# diagnostic-main.net
KiCad netlist of a schematic drawn in EAGLE
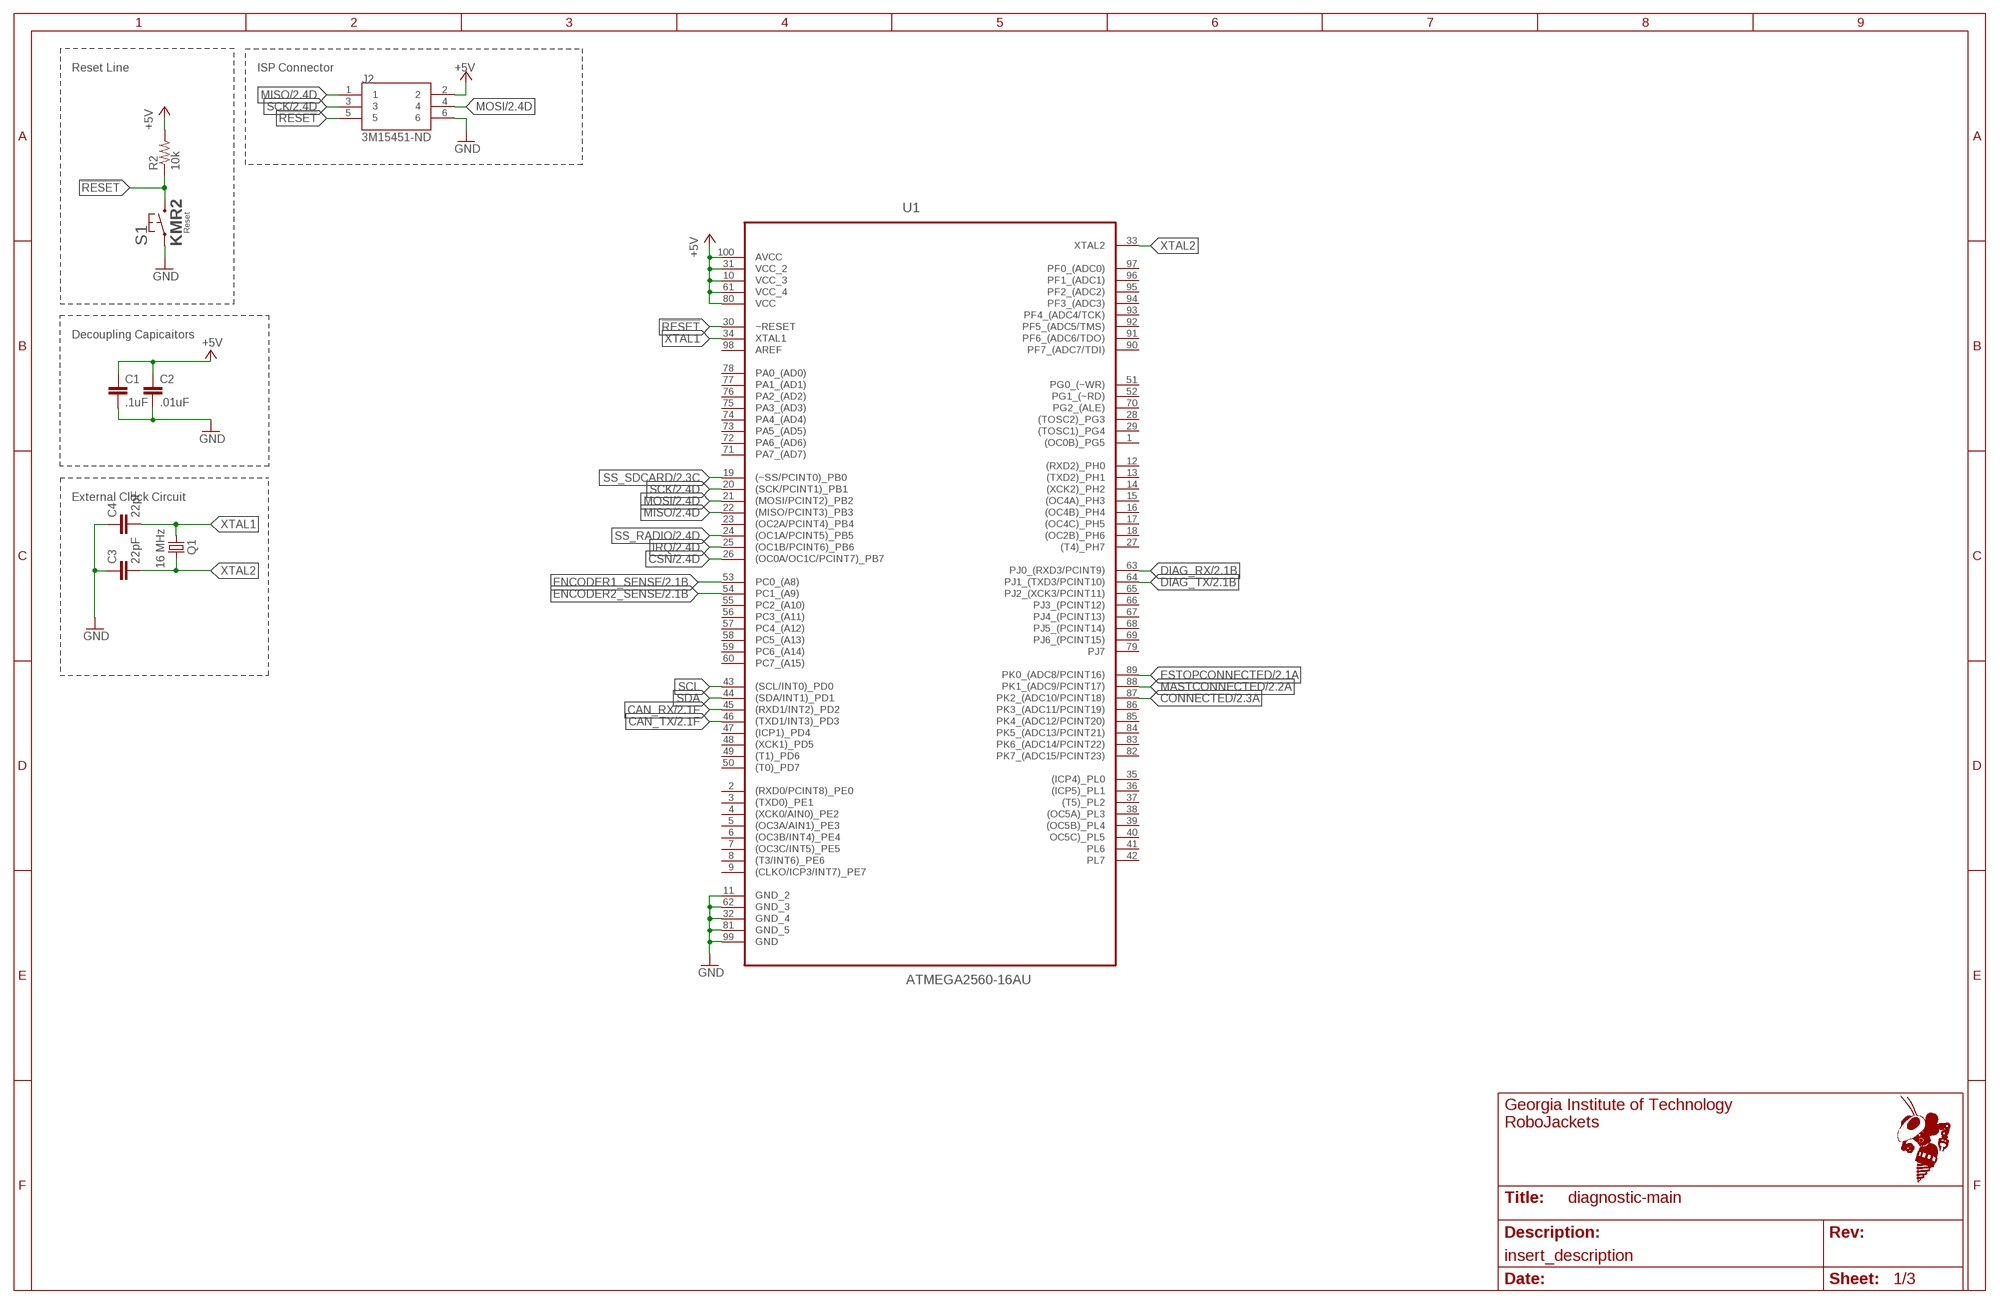
[diagram p0: schematic, sheet 1]
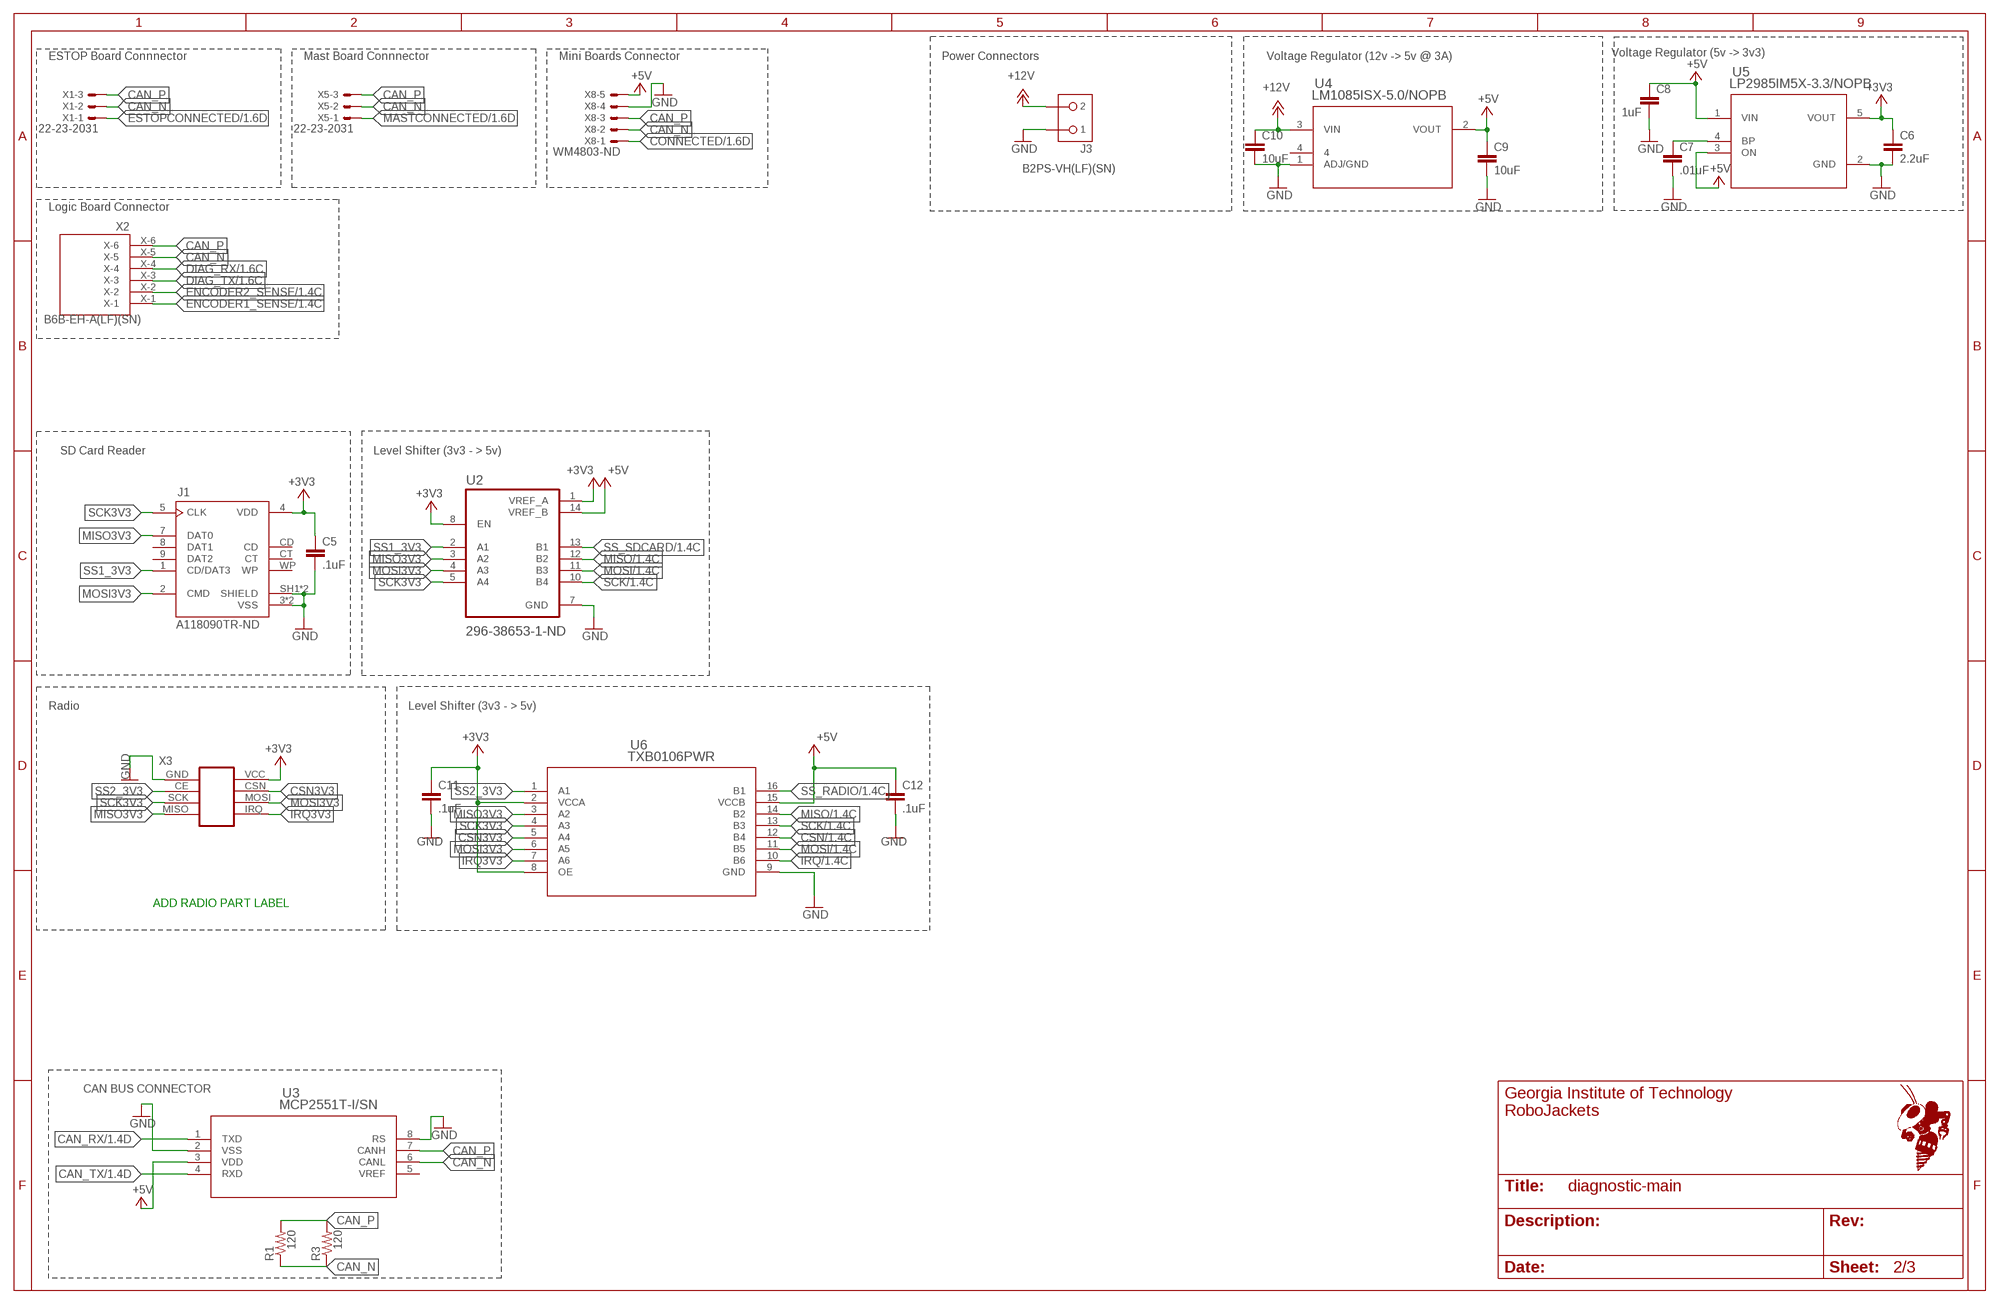
[diagram p1: schematic, sheet 2]

(export (version "E")
  (design (tool "Eeschema 10.0.6"))
  (components
    (comp (ref "C5")
      (value ".1uF")
      (footprint "eagle-import:C0603")
      (libsource (lib "eagle-import") (part "C-EUC0603"))
    )
    (comp (ref "C6")
      (value "2.2uF")
      (footprint "eagle-import:C0603")
      (libsource (lib "eagle-import") (part "C-EUC0603"))
    )
    (comp (ref "C7")
      (value ".01uF")
      (footprint "eagle-import:C0603")
      (libsource (lib "eagle-import") (part "C-EUC0603"))
    )
    (comp (ref "C8")
      (value "1uF")
      (footprint "eagle-import:C0603")
      (libsource (lib "eagle-import") (part "C-EUC0603"))
    )
    (comp (ref "C9")
      (value "10uF")
      (footprint "eagle-import:C0805")
      (libsource (lib "eagle-import") (part "C-EUC0805"))
    )
    (comp (ref "C10")
      (value "10uF")
      (footprint "eagle-import:C0805")
      (libsource (lib "eagle-import") (part "C-EUC0805"))
    )
    (comp (ref "C11")
      (value ".1uF")
      (footprint "eagle-import:C0603")
      (libsource (lib "eagle-import") (part "C-EUC0603"))
    )
    (comp (ref "C12")
      (value ".1uF")
      (footprint "eagle-import:C0603")
      (libsource (lib "eagle-import") (part "C-EUC0603"))
    )
    (comp (ref "J1")
      (value "A118090TR-ND")
      (footprint "eagle-import:TE_1939870-1")
      (fields
        (field (name "COMMENT") "1939870-1")
        (field (name "DIGI-KEY_PART_NUMBER") "A118090CT-ND")
        (field (name "MF") "TE Connectivity")
      )
      (libsource (lib "eagle-import") (part "1939870-1"))
    )
    (comp (ref "J3")
      (value "B2PS-VH(LF)(SN)")
      (footprint "eagle-import:B2PS-CENTERED")
      (libsource (lib "eagle-import") (part "B2P?-VH(LF)(SN)S"))
    )
    (comp (ref "R1")
      (value "120")
      (footprint "eagle-import:R0402")
      (libsource (lib "eagle-import") (part "R-US_R0402"))
    )
    (comp (ref "R3")
      (value "120")
      (footprint "eagle-import:R0402")
      (libsource (lib "eagle-import") (part "R-US_R0402"))
    )
    (comp (ref "U2")
      (value "296-38653-1-ND")
      (footprint "eagle-import:SOP65P640X120-14N")
      (fields (field (name "MF") "Texas Instruments") (field (name "MP") "LSF0204PWR"))
      (libsource (lib "eagle-import") (part "LSF0204PWR"))
    )
    (comp (ref "U3")
      (value "MCP2551T-I/SN")
      (footprint "eagle-import:SOIC8-N_MC")
      (fields (field (name "MANUFACTURER_PART_NUMBER") "MCP2551TISN"))
      (libsource (lib "eagle-import") (part "MCP2551T-I/SN"))
    )
    (comp (ref "U4")
      (value "LM1085ISX-5.0/NOPB")
      (footprint "eagle-import:TS3B")
      (fields (field (name "MANUFACTURER_PART_NUMBER") "LM1085ISX5.0NOPB"))
      (libsource (lib "eagle-import") (part "LM1085ISX-5.0/NOPB"))
    )
    (comp (ref "U5")
      (value "LP2985IM5X-3.3/NOPB")
      (footprint "eagle-import:MF05A")
      (fields (field (name "MANUFACTURER_PART_NUMBER") "LP2985IM5X3.3NOPB"))
      (libsource (lib "eagle-import") (part "LP2985IM5X-3.3/NOPB"))
    )
    (comp (ref "U6")
      (value "TXB0106PWR")
      (footprint "eagle-import:PW16")
      (libsource (lib "eagle-import") (part "TXB0106PWR"))
    )
    (comp (ref "X1")
      (value "22-23-2031")
      (footprint "eagle-import:22-23-2031")
      (fields (field (name "MF") "MOLEX"))
      (libsource (lib "eagle-import") (part "22-23-2031"))
    )
    (comp (ref "X2")
      (value "B6B-EH-A(LF)(SN)")
      (footprint "eagle-import:B6BEHALFSN")
      (libsource (lib "eagle-import") (part "B6B-EH-A(LF)(SN)"))
    )
    (comp (ref "X3")
      (value "NRF24L01+PA+LNA")
      (footprint "eagle-import:NRF24L01+PA+LNA")
      (libsource (lib "eagle-import") (part "NRF24L01+PA+LNA"))
    )
    (comp (ref "X5")
      (value "22-23-2031")
      (footprint "eagle-import:22-23-2031")
      (fields (field (name "MF") "MOLEX"))
      (libsource (lib "eagle-import") (part "22-23-2031"))
    )
    (comp (ref "X8")
      (value "WM4803-ND")
      (footprint "eagle-import:22-23-2051")
      (fields (field (name "MF") "MOLEX") (field (name "MPN") "22-23-2051"))
      (libsource (lib "eagle-import") (part "22-23-2051"))
    )
    (comp (ref "C1")
      (value ".1uF")
      (footprint "eagle-import:C0603")
      (libsource (lib "eagle-import") (part "C-EUC0603"))
    )
    (comp (ref "C2")
      (value ".01uF")
      (footprint "eagle-import:C0603")
      (libsource (lib "eagle-import") (part "C-EUC0603"))
    )
    (comp (ref "C3")
      (value "22pF")
      (footprint "eagle-import:C0603")
      (libsource (lib "eagle-import") (part "C-EUC0603"))
    )
    (comp (ref "C4")
      (value "22pF")
      (footprint "eagle-import:C0603")
      (libsource (lib "eagle-import") (part "C-EUC0603"))
    )
    (comp (ref "J2")
      (value "3M15451-ND")
      (footprint "eagle-import:3M_30306-6002HB")
      (fields (field (name "MF") "3M") (field (name "MP") "30306-6002HB"))
      (libsource (lib "eagle-import") (part "30306-6002HB"))
    )
    (comp (ref "Q1")
      (value "16 MHz")
      (footprint "eagle-import:CSM-7X-DU")
      (libsource (lib "eagle-import") (part "CSM-7X-DU"))
    )
    (comp (ref "R2")
      (value "10k")
      (footprint "eagle-import:R0402")
      (libsource (lib "eagle-import") (part "R-US_R0402"))
    )
    (comp (ref "S1")
      (value "KMR2")
      (footprint "eagle-import:KMR2")
      (fields (field (name "FUNCTION") "Reset"))
      (libsource (lib "eagle-import") (part "KMR2"))
    )
    (comp (ref "U1")
      (value "ATMEGA2560-16AU")
      (footprint "eagle-import:QFP50P1600X1600X120-100N")
      (fields (field (name "MF") "Microchip"))
      (libsource (lib "eagle-import") (part "ATMEGA2560-16AU"))
    )
  )
  (nets
    (net (code "1") (name "+3V3") (class "Default")
      (node (ref "C11") (pin "1") (pinfunction "1_1") (pintype "passive"))
      (node (ref "C5") (pin "1") (pinfunction "1_1") (pintype "passive"))
      (node (ref "C6") (pin "1") (pinfunction "1_1") (pintype "passive"))
      (node (ref "J1") (pin "4") (pinfunction "VDD_4") (pintype "power_in"))
      (node (ref "U2") (pin "1") (pinfunction "VREF_A_1") (pintype "power_in"))
      (node (ref "U2") (pin "8") (pinfunction "EN_8") (pintype "input"))
      (node (ref "U5") (pin "5") (pinfunction "VOUT_5") (pintype "output"))
      (node (ref "U6") (pin "2") (pinfunction "VCCA_2") (pintype "power_in"))
      (node (ref "U6") (pin "8") (pinfunction "OE_8") (pintype "output"))
      (node (ref "X3") (pin "VCC") (pinfunction "VCC_VCC") (pintype "power_in"))
    )
    (net (code "2") (name "+5V") (class "Default")
      (node (ref "C1") (pin "1") (pinfunction "1_1") (pintype "passive"))
      (node (ref "C12") (pin "1") (pinfunction "1_1") (pintype "passive"))
      (node (ref "C2") (pin "1") (pinfunction "1_1") (pintype "passive"))
      (node (ref "C8") (pin "1") (pinfunction "1_1") (pintype "passive"))
      (node (ref "C9") (pin "1") (pinfunction "1_1") (pintype "passive"))
      (node (ref "J2") (pin "2") (pinfunction "2_2") (pintype "passive"))
      (node (ref "R2") (pin "2") (pinfunction "2_2") (pintype "passive"))
      (node (ref "U1") (pin "10") (pinfunction "VCC_3_10") (pintype "power_in"))
      (node (ref "U1") (pin "100") (pinfunction "AVCC_100") (pintype "power_in"))
      (node (ref "U1") (pin "31") (pinfunction "VCC_2_31") (pintype "power_in"))
      (node (ref "U1") (pin "61") (pinfunction "VCC_4_61") (pintype "power_in"))
      (node (ref "U1") (pin "80") (pinfunction "VCC_80") (pintype "power_in"))
      (node (ref "U2") (pin "14") (pinfunction "VREF_B_14") (pintype "power_in"))
      (node (ref "U3") (pin "3") (pinfunction "VDD_3") (pintype "passive"))
      (node (ref "U4") (pin "2") (pinfunction "VOUT_2") (pintype "output"))
      (node (ref "U5") (pin "1") (pinfunction "VIN_1") (pintype "input"))
      (node (ref "U5") (pin "3") (pinfunction "ON_3") (pintype "passive"))
      (node (ref "U6") (pin "15") (pinfunction "VCCB_15") (pintype "power_in"))
      (node (ref "X8") (pin "5") (pinfunction "S_5") (pintype "passive"))
    )
    (net (code "3") (name "+12V") (class "Default")
      (node (ref "C10") (pin "1") (pinfunction "1_1") (pintype "passive"))
      (node (ref "J3") (pin "2") (pinfunction "2_2") (pintype "bidirectional"))
      (node (ref "U4") (pin "3") (pinfunction "VIN_3") (pintype "input"))
    )
    (net (code "4") (name "CAN_N") (class "Default")
      (node (ref "R1") (pin "1") (pinfunction "1_1") (pintype "passive"))
      (node (ref "R3") (pin "1") (pinfunction "1_1") (pintype "passive"))
      (node (ref "U3") (pin "6") (pinfunction "CANL_6") (pintype "passive"))
      (node (ref "X1") (pin "2") (pinfunction "S_2") (pintype "passive"))
      (node (ref "X2") (pin "X-5") (pinfunction "X-5_X-5") (pintype "bidirectional"))
      (node (ref "X5") (pin "2") (pinfunction "S_2") (pintype "passive"))
      (node (ref "X8") (pin "2") (pinfunction "S_2") (pintype "passive"))
    )
    (net (code "5") (name "CAN_P") (class "Default")
      (node (ref "R1") (pin "2") (pinfunction "2_2") (pintype "passive"))
      (node (ref "R3") (pin "2") (pinfunction "2_2") (pintype "passive"))
      (node (ref "U3") (pin "7") (pinfunction "CANH_7") (pintype "passive"))
      (node (ref "X1") (pin "3") (pinfunction "S_3") (pintype "passive"))
      (node (ref "X2") (pin "X-6") (pinfunction "X-6_X-6") (pintype "bidirectional"))
      (node (ref "X5") (pin "3") (pinfunction "S_3") (pintype "passive"))
      (node (ref "X8") (pin "3") (pinfunction "S_3") (pintype "passive"))
    )
    (net (code "6") (name "CAN_RX") (class "Default")
      (node (ref "U1") (pin "45") (pinfunction "(RXD1/INT2)_PD2_45") (pintype "bidirectional"))
      (node (ref "U3") (pin "1") (pinfunction "TXD_1") (pintype "passive"))
    )
    (net (code "7") (name "CAN_TX") (class "Default")
      (node (ref "U1") (pin "46") (pinfunction "(TXD1/INT3)_PD3_46") (pintype "bidirectional"))
      (node (ref "U3") (pin "4") (pinfunction "RXD_4") (pintype "passive"))
    )
    (net (code "8") (name "CONNECTED") (class "Default")
      (node (ref "U1") (pin "87") (pinfunction "PK2_(ADC10/PCINT18)_87") (pintype "bidirectional"))
      (node (ref "X8") (pin "1") (pinfunction "S_1") (pintype "passive"))
    )
    (net (code "9") (name "CSN") (class "Default")
      (node (ref "U1") (pin "26") (pinfunction "(OC0A/OC1C/PCINT7)_PB7_26") (pintype "bidirectional"))
      (node (ref "U6") (pin "12") (pinfunction "B4_12") (pintype "bidirectional"))
    )
    (net (code "10") (name "CSN3V3") (class "Default")
      (node (ref "U6") (pin "5") (pinfunction "A4_5") (pintype "bidirectional"))
      (node (ref "X3") (pin "CSN") (pinfunction "CSN_CSN") (pintype "passive"))
    )
    (net (code "11") (name "DIAG_RX") (class "Default")
      (node (ref "U1") (pin "63") (pinfunction "PJ0_(RXD3/PCINT9)_63") (pintype "bidirectional"))
      (node (ref "X2") (pin "X-4") (pinfunction "X-4_X-4") (pintype "bidirectional"))
    )
    (net (code "12") (name "DIAG_TX") (class "Default")
      (node (ref "U1") (pin "64") (pinfunction "PJ1_(TXD3/PCINT10)_64") (pintype "bidirectional"))
      (node (ref "X2") (pin "X-3") (pinfunction "X-3_X-3") (pintype "bidirectional"))
    )
    (net (code "13") (name "ENCODER1_SENSE") (class "Default")
      (node (ref "U1") (pin "53") (pinfunction "PC0_(A8)_53") (pintype "bidirectional"))
      (node (ref "X2") (pin "X-1") (pinfunction "X-1_X-1") (pintype "bidirectional"))
    )
    (net (code "14") (name "ENCODER2_SENSE") (class "Default")
      (node (ref "U1") (pin "54") (pinfunction "PC1_(A9)_54") (pintype "bidirectional"))
      (node (ref "X2") (pin "X-2") (pinfunction "X-2_X-2") (pintype "bidirectional"))
    )
    (net (code "15") (name "ESTOPCONNECTED") (class "Default")
      (node (ref "U1") (pin "89") (pinfunction "PK0_(ADC8/PCINT16)_89") (pintype "bidirectional"))
      (node (ref "X1") (pin "1") (pinfunction "S_1") (pintype "passive"))
    )
    (net (code "16") (name "GND") (class "Default")
      (node (ref "C1") (pin "2") (pinfunction "2_2") (pintype "passive"))
      (node (ref "C10") (pin "2") (pinfunction "2_2") (pintype "passive"))
      (node (ref "C11") (pin "2") (pinfunction "2_2") (pintype "passive"))
      (node (ref "C12") (pin "2") (pinfunction "2_2") (pintype "passive"))
      (node (ref "C2") (pin "2") (pinfunction "2_2") (pintype "passive"))
      (node (ref "C3") (pin "1") (pinfunction "1_1") (pintype "passive"))
      (node (ref "C4") (pin "1") (pinfunction "1_1") (pintype "passive"))
      (node (ref "C5") (pin "2") (pinfunction "2_2") (pintype "passive"))
      (node (ref "C6") (pin "2") (pinfunction "2_2") (pintype "passive"))
      (node (ref "C7") (pin "2") (pinfunction "2_2") (pintype "passive"))
      (node (ref "C8") (pin "2") (pinfunction "2_2") (pintype "passive"))
      (node (ref "C9") (pin "2") (pinfunction "2_2") (pintype "passive"))
      (node (ref "J1") (pin "3") (pinfunction "VSS_3") (pintype "power_in"))
      (node (ref "J1") (pin "6") (pinfunction "VSS_6") (pintype "power_in"))
      (node (ref "J1") (pin "SH1") (pinfunction "SHIELD_SH1") (pintype "passive"))
      (node (ref "J1") (pin "SH2") (pinfunction "SHIELD_SH2") (pintype "passive"))
      (node (ref "J2") (pin "6") (pinfunction "6_6") (pintype "passive"))
      (node (ref "J3") (pin "1") (pinfunction "1_1") (pintype "bidirectional"))
      (node (ref "S1") (pin "1.1") (pinfunction "1_1.1") (pintype "passive"))
      (node (ref "S1") (pin "1.2") (pinfunction "1_1.2") (pintype "passive"))
      (node (ref "U1") (pin "11") (pinfunction "GND_2_11") (pintype "passive"))
      (node (ref "U1") (pin "32") (pinfunction "GND_4_32") (pintype "passive"))
      (node (ref "U1") (pin "62") (pinfunction "GND_3_62") (pintype "passive"))
      (node (ref "U1") (pin "81") (pinfunction "GND_5_81") (pintype "passive"))
      (node (ref "U1") (pin "99") (pinfunction "GND_99") (pintype "passive"))
      (node (ref "U2") (pin "7") (pinfunction "GND_7") (pintype "power_in"))
      (node (ref "U3") (pin "2") (pinfunction "VSS_2") (pintype "passive"))
      (node (ref "U3") (pin "8") (pinfunction "RS_8") (pintype "passive"))
      (node (ref "U4") (pin "1") (pinfunction "ADJ/GND_1") (pintype "passive"))
      (node (ref "U5") (pin "2") (pinfunction "GND_2") (pintype "passive"))
      (node (ref "U6") (pin "9") (pinfunction "GND_9") (pintype "power_in"))
      (node (ref "X3") (pin "GND") (pinfunction "GND_GND") (pintype "power_in"))
      (node (ref "X8") (pin "4") (pinfunction "S_4") (pintype "passive"))
    )
    (net (code "17") (name "IRQ") (class "Default")
      (node (ref "U1") (pin "25") (pinfunction "(OC1B/PCINT6)_PB6_25") (pintype "bidirectional"))
      (node (ref "U6") (pin "10") (pinfunction "B6_10") (pintype "bidirectional"))
    )
    (net (code "18") (name "IRQ3V3") (class "Default")
      (node (ref "U6") (pin "7") (pinfunction "A6_7") (pintype "bidirectional"))
      (node (ref "X3") (pin "IRQ") (pinfunction "IRQ_IRQ") (pintype "passive"))
    )
    (net (code "19") (name "MASTCONNECTED") (class "Default")
      (node (ref "U1") (pin "88") (pinfunction "PK1_(ADC9/PCINT17)_88") (pintype "bidirectional"))
      (node (ref "X5") (pin "1") (pinfunction "S_1") (pintype "passive"))
    )
    (net (code "20") (name "MISO") (class "Default")
      (node (ref "J2") (pin "1") (pinfunction "1_1") (pintype "passive"))
      (node (ref "U1") (pin "22") (pinfunction "(MISO/PCINT3)_PB3_22") (pintype "bidirectional"))
      (node (ref "U2") (pin "12") (pinfunction "B2_12") (pintype "bidirectional"))
      (node (ref "U6") (pin "14") (pinfunction "B2_14") (pintype "bidirectional"))
    )
    (net (code "21") (name "MISO3V3") (class "Default")
      (node (ref "J1") (pin "7") (pinfunction "DAT0_7") (pintype "bidirectional"))
      (node (ref "U2") (pin "3") (pinfunction "A2_3") (pintype "bidirectional"))
      (node (ref "U6") (pin "3") (pinfunction "A2_3") (pintype "bidirectional"))
      (node (ref "X3") (pin "MISO") (pinfunction "MISO_MISO") (pintype "passive"))
    )
    (net (code "22") (name "MOSI") (class "Default")
      (node (ref "J2") (pin "4") (pinfunction "4_4") (pintype "passive"))
      (node (ref "U1") (pin "21") (pinfunction "(MOSI/PCINT2)_PB2_21") (pintype "bidirectional"))
      (node (ref "U2") (pin "11") (pinfunction "B3_11") (pintype "bidirectional"))
      (node (ref "U6") (pin "11") (pinfunction "B5_11") (pintype "bidirectional"))
    )
    (net (code "23") (name "MOSI3V3") (class "Default")
      (node (ref "J1") (pin "2") (pinfunction "CMD_2") (pintype "passive"))
      (node (ref "U2") (pin "4") (pinfunction "A3_4") (pintype "bidirectional"))
      (node (ref "U6") (pin "6") (pinfunction "A5_6") (pintype "bidirectional"))
      (node (ref "X3") (pin "MOSI") (pinfunction "MOSI_MOSI") (pintype "passive"))
    )
    (net (code "24") (name "Net-(U5-BP)") (class "Default")
      (node (ref "C7") (pin "1") (pinfunction "1_1") (pintype "passive"))
      (node (ref "U5") (pin "4") (pinfunction "BP_4") (pintype "passive"))
    )
    (net (code "25") (name "SCK") (class "Default")
      (node (ref "J2") (pin "3") (pinfunction "3_3") (pintype "passive"))
      (node (ref "U1") (pin "20") (pinfunction "(SCK/PCINT1)_PB1_20") (pintype "bidirectional"))
      (node (ref "U2") (pin "10") (pinfunction "B4_10") (pintype "bidirectional"))
      (node (ref "U6") (pin "13") (pinfunction "B3_13") (pintype "bidirectional"))
    )
    (net (code "26") (name "SCK3V3") (class "Default")
      (node (ref "J1") (pin "5") (pinfunction "CLK_5") (pintype "input"))
      (node (ref "U2") (pin "5") (pinfunction "A4_5") (pintype "bidirectional"))
      (node (ref "U6") (pin "4") (pinfunction "A3_4") (pintype "bidirectional"))
      (node (ref "X3") (pin "SCK") (pinfunction "SCK_SCK") (pintype "passive"))
    )
    (net (code "27") (name "SCL") (class "Default")
      (node (ref "U1") (pin "43") (pinfunction "(SCL/INT0)_PD0_43") (pintype "bidirectional"))
    )
    (net (code "28") (name "SDA") (class "Default")
      (node (ref "U1") (pin "44") (pinfunction "(SDA/INT1)_PD1_44") (pintype "bidirectional"))
    )
    (net (code "29") (name "SS1_3V3") (class "Default")
      (node (ref "J1") (pin "1") (pinfunction "CD/DAT3_1") (pintype "bidirectional"))
      (node (ref "U2") (pin "2") (pinfunction "A1_2") (pintype "bidirectional"))
    )
    (net (code "30") (name "SS2_3V3") (class "Default")
      (node (ref "U6") (pin "1") (pinfunction "A1_1") (pintype "bidirectional"))
      (node (ref "X3") (pin "CE") (pinfunction "CE_CE") (pintype "passive"))
    )
    (net (code "31") (name "SS_RADIO") (class "Default")
      (node (ref "U1") (pin "24") (pinfunction "(OC1A/PCINT5)_PB5_24") (pintype "bidirectional"))
      (node (ref "U6") (pin "16") (pinfunction "B1_16") (pintype "bidirectional"))
    )
    (net (code "32") (name "SS_SDCARD") (class "Default")
      (node (ref "U1") (pin "19") (pinfunction "(~{SS/PCINT0})_PB0_19") (pintype "bidirectional"))
      (node (ref "U2") (pin "13") (pinfunction "B1_13") (pintype "bidirectional"))
    )
    (net (code "33") (name "XTAL1") (class "Default")
      (node (ref "C4") (pin "2") (pinfunction "2_2") (pintype "passive"))
      (node (ref "Q1") (pin "1") (pinfunction "1_1") (pintype "passive"))
      (node (ref "U1") (pin "34") (pinfunction "XTAL1_34") (pintype "input"))
    )
    (net (code "34") (name "XTAL2") (class "Default")
      (node (ref "C3") (pin "2") (pinfunction "2_2") (pintype "passive"))
      (node (ref "Q1") (pin "2") (pinfunction "2_2") (pintype "passive"))
      (node (ref "U1") (pin "33") (pinfunction "XTAL2_33") (pintype "output"))
    )
    (net (code "35") (name "unconnected-(J1-DAT1-Pad8)") (class "Default")
      (node (ref "J1") (pin "8") (pinfunction "DAT1_8") (pintype "bidirectional"))
    )
    (net (code "36") (name "unconnected-(J1-DAT2-Pad9)") (class "Default")
      (node (ref "J1") (pin "9") (pinfunction "DAT2_9") (pintype "bidirectional"))
    )
    (net (code "37") (name "unconnected-(J1-PadCD)") (class "Default")
      (node (ref "J1") (pin "CD") (pinfunction "CD_CD") (pintype "passive"))
    )
    (net (code "38") (name "unconnected-(J1-PadCT)") (class "Default")
      (node (ref "J1") (pin "CT") (pinfunction "CT_CT") (pintype "passive"))
    )
    (net (code "39") (name "unconnected-(J1-PadWP)") (class "Default")
      (node (ref "J1") (pin "WP") (pinfunction "WP_WP") (pintype "passive"))
    )
    (net (code "40") (name "unconnected-(U1-(CLKO{slash}ICP3{slash}INT7)_PE7-Pad9)") (class "Default")
      (node (ref "U1") (pin "9") (pinfunction "(CLKO/ICP3/INT7)_PE7_9") (pintype "bidirectional"))
    )
    (net (code "41") (name "unconnected-(U1-(ICP1)_PD4-Pad47)") (class "Default")
      (node (ref "U1") (pin "47") (pinfunction "(ICP1)_PD4_47") (pintype "bidirectional"))
    )
    (net (code "42") (name "unconnected-(U1-(ICP4)_PL0-Pad35)") (class "Default")
      (node (ref "U1") (pin "35") (pinfunction "(ICP4)_PL0_35") (pintype "bidirectional"))
    )
    (net (code "43") (name "unconnected-(U1-(ICP5)_PL1-Pad36)") (class "Default")
      (node (ref "U1") (pin "36") (pinfunction "(ICP5)_PL1_36") (pintype "bidirectional"))
    )
    (net (code "44") (name "unconnected-(U1-(OC0B)_PG5-Pad1)") (class "Default")
      (node (ref "U1") (pin "1") (pinfunction "(OC0B)_PG5_1") (pintype "bidirectional"))
    )
    (net (code "45") (name "unconnected-(U1-(OC2A{slash}PCINT4)_PB4-Pad23)") (class "Default")
      (node (ref "U1") (pin "23") (pinfunction "(OC2A/PCINT4)_PB4_23") (pintype "bidirectional"))
    )
    (net (code "46") (name "unconnected-(U1-(OC2B)_PH6-Pad18)") (class "Default")
      (node (ref "U1") (pin "18") (pinfunction "(OC2B)_PH6_18") (pintype "bidirectional"))
    )
    (net (code "47") (name "unconnected-(U1-(OC3A{slash}AIN1)_PE3-Pad5)") (class "Default")
      (node (ref "U1") (pin "5") (pinfunction "(OC3A/AIN1)_PE3_5") (pintype "bidirectional"))
    )
    (net (code "48") (name "unconnected-(U1-(OC3B{slash}INT4)_PE4-Pad6)") (class "Default")
      (node (ref "U1") (pin "6") (pinfunction "(OC3B/INT4)_PE4_6") (pintype "bidirectional"))
    )
    (net (code "49") (name "unconnected-(U1-(OC3C{slash}INT5)_PE5-Pad7)") (class "Default")
      (node (ref "U1") (pin "7") (pinfunction "(OC3C/INT5)_PE5_7") (pintype "bidirectional"))
    )
    (net (code "50") (name "unconnected-(U1-(OC4A)_PH3-Pad15)") (class "Default")
      (node (ref "U1") (pin "15") (pinfunction "(OC4A)_PH3_15") (pintype "bidirectional"))
    )
    (net (code "51") (name "unconnected-(U1-(OC4B)_PH4-Pad16)") (class "Default")
      (node (ref "U1") (pin "16") (pinfunction "(OC4B)_PH4_16") (pintype "bidirectional"))
    )
    (net (code "52") (name "unconnected-(U1-(OC4C)_PH5-Pad17)") (class "Default")
      (node (ref "U1") (pin "17") (pinfunction "(OC4C)_PH5_17") (pintype "bidirectional"))
    )
    (net (code "53") (name "unconnected-(U1-(OC5A)_PL3-Pad38)") (class "Default")
      (node (ref "U1") (pin "38") (pinfunction "(OC5A)_PL3_38") (pintype "bidirectional"))
    )
    (net (code "54") (name "unconnected-(U1-(OC5B)_PL4-Pad39)") (class "Default")
      (node (ref "U1") (pin "39") (pinfunction "(OC5B)_PL4_39") (pintype "bidirectional"))
    )
    (net (code "55") (name "unconnected-(U1-(RXD0{slash}PCINT8)_PE0-Pad2)") (class "Default")
      (node (ref "U1") (pin "2") (pinfunction "(RXD0/PCINT8)_PE0_2") (pintype "bidirectional"))
    )
    (net (code "56") (name "unconnected-(U1-(RXD2)_PH0-Pad12)") (class "Default")
      (node (ref "U1") (pin "12") (pinfunction "(RXD2)_PH0_12") (pintype "bidirectional"))
    )
    (net (code "57") (name "unconnected-(U1-(T0)_PD7-Pad50)") (class "Default")
      (node (ref "U1") (pin "50") (pinfunction "(T0)_PD7_50") (pintype "bidirectional"))
    )
    (net (code "58") (name "unconnected-(U1-(T1)_PD6-Pad49)") (class "Default")
      (node (ref "U1") (pin "49") (pinfunction "(T1)_PD6_49") (pintype "bidirectional"))
    )
    (net (code "59") (name "unconnected-(U1-(T3{slash}INT6)_PE6-Pad8)") (class "Default")
      (node (ref "U1") (pin "8") (pinfunction "(T3/INT6)_PE6_8") (pintype "bidirectional"))
    )
    (net (code "60") (name "unconnected-(U1-(T4)_PH7-Pad27)") (class "Default")
      (node (ref "U1") (pin "27") (pinfunction "(T4)_PH7_27") (pintype "bidirectional"))
    )
    (net (code "61") (name "unconnected-(U1-(T5)_PL2-Pad37)") (class "Default")
      (node (ref "U1") (pin "37") (pinfunction "(T5)_PL2_37") (pintype "bidirectional"))
    )
    (net (code "62") (name "unconnected-(U1-(TOSC1)_PG4-Pad29)") (class "Default")
      (node (ref "U1") (pin "29") (pinfunction "(TOSC1)_PG4_29") (pintype "bidirectional"))
    )
    (net (code "63") (name "unconnected-(U1-(TOSC2)_PG3-Pad28)") (class "Default")
      (node (ref "U1") (pin "28") (pinfunction "(TOSC2)_PG3_28") (pintype "bidirectional"))
    )
    (net (code "64") (name "unconnected-(U1-(TXD0)_PE1-Pad3)") (class "Default")
      (node (ref "U1") (pin "3") (pinfunction "(TXD0)_PE1_3") (pintype "bidirectional"))
    )
    (net (code "65") (name "unconnected-(U1-(TXD2)_PH1-Pad13)") (class "Default")
      (node (ref "U1") (pin "13") (pinfunction "(TXD2)_PH1_13") (pintype "bidirectional"))
    )
    (net (code "66") (name "unconnected-(U1-(XCK0{slash}AIN0)_PE2-Pad4)") (class "Default")
      (node (ref "U1") (pin "4") (pinfunction "(XCK0/AIN0)_PE2_4") (pintype "bidirectional"))
    )
    (net (code "67") (name "unconnected-(U1-(XCK1)_PD5-Pad48)") (class "Default")
      (node (ref "U1") (pin "48") (pinfunction "(XCK1)_PD5_48") (pintype "bidirectional"))
    )
    (net (code "68") (name "unconnected-(U1-(XCK2)_PH2-Pad14)") (class "Default")
      (node (ref "U1") (pin "14") (pinfunction "(XCK2)_PH2_14") (pintype "bidirectional"))
    )
    (net (code "69") (name "unconnected-(U1-AREF-Pad98)") (class "Default")
      (node (ref "U1") (pin "98") (pinfunction "AREF_98") (pintype "input"))
    )
    (net (code "70") (name "unconnected-(U1-OC5C)_PL5-Pad40)") (class "Default")
      (node (ref "U1") (pin "40") (pinfunction "OC5C)_PL5_40") (pintype "bidirectional"))
    )
    (net (code "71") (name "unconnected-(U1-PA0_(AD0)-Pad78)") (class "Default")
      (node (ref "U1") (pin "78") (pinfunction "PA0_(AD0)_78") (pintype "bidirectional"))
    )
    (net (code "72") (name "unconnected-(U1-PA1_(AD1)-Pad77)") (class "Default")
      (node (ref "U1") (pin "77") (pinfunction "PA1_(AD1)_77") (pintype "bidirectional"))
    )
    (net (code "73") (name "unconnected-(U1-PA2_(AD2)-Pad76)") (class "Default")
      (node (ref "U1") (pin "76") (pinfunction "PA2_(AD2)_76") (pintype "bidirectional"))
    )
    (net (code "74") (name "unconnected-(U1-PA3_(AD3)-Pad75)") (class "Default")
      (node (ref "U1") (pin "75") (pinfunction "PA3_(AD3)_75") (pintype "bidirectional"))
    )
    (net (code "75") (name "unconnected-(U1-PA4_(AD4)-Pad74)") (class "Default")
      (node (ref "U1") (pin "74") (pinfunction "PA4_(AD4)_74") (pintype "bidirectional"))
    )
    (net (code "76") (name "unconnected-(U1-PA5_(AD5)-Pad73)") (class "Default")
      (node (ref "U1") (pin "73") (pinfunction "PA5_(AD5)_73") (pintype "bidirectional"))
    )
    (net (code "77") (name "unconnected-(U1-PA6_(AD6)-Pad72)") (class "Default")
      (node (ref "U1") (pin "72") (pinfunction "PA6_(AD6)_72") (pintype "bidirectional"))
    )
    (net (code "78") (name "unconnected-(U1-PA7_(AD7)-Pad71)") (class "Default")
      (node (ref "U1") (pin "71") (pinfunction "PA7_(AD7)_71") (pintype "bidirectional"))
    )
    (net (code "79") (name "unconnected-(U1-PC2_(A10)-Pad55)") (class "Default")
      (node (ref "U1") (pin "55") (pinfunction "PC2_(A10)_55") (pintype "bidirectional"))
    )
    (net (code "80") (name "unconnected-(U1-PC3_(A11)-Pad56)") (class "Default")
      (node (ref "U1") (pin "56") (pinfunction "PC3_(A11)_56") (pintype "bidirectional"))
    )
    (net (code "81") (name "unconnected-(U1-PC4_(A12)-Pad57)") (class "Default")
      (node (ref "U1") (pin "57") (pinfunction "PC4_(A12)_57") (pintype "bidirectional"))
    )
    (net (code "82") (name "unconnected-(U1-PC5_(A13)-Pad58)") (class "Default")
      (node (ref "U1") (pin "58") (pinfunction "PC5_(A13)_58") (pintype "bidirectional"))
    )
    (net (code "83") (name "unconnected-(U1-PC6_(A14)-Pad59)") (class "Default")
      (node (ref "U1") (pin "59") (pinfunction "PC6_(A14)_59") (pintype "bidirectional"))
    )
    (net (code "84") (name "unconnected-(U1-PC7_(A15)-Pad60)") (class "Default")
      (node (ref "U1") (pin "60") (pinfunction "PC7_(A15)_60") (pintype "bidirectional"))
    )
    (net (code "85") (name "unconnected-(U1-PF0_(ADC0)-Pad97)") (class "Default")
      (node (ref "U1") (pin "97") (pinfunction "PF0_(ADC0)_97") (pintype "bidirectional"))
    )
    (net (code "86") (name "unconnected-(U1-PF1_(ADC1)-Pad96)") (class "Default")
      (node (ref "U1") (pin "96") (pinfunction "PF1_(ADC1)_96") (pintype "bidirectional"))
    )
    (net (code "87") (name "unconnected-(U1-PF2_(ADC2)-Pad95)") (class "Default")
      (node (ref "U1") (pin "95") (pinfunction "PF2_(ADC2)_95") (pintype "bidirectional"))
    )
    (net (code "88") (name "unconnected-(U1-PF3_(ADC3)-Pad94)") (class "Default")
      (node (ref "U1") (pin "94") (pinfunction "PF3_(ADC3)_94") (pintype "bidirectional"))
    )
    (net (code "89") (name "unconnected-(U1-PF4_(ADC4{slash}TCK)-Pad93)") (class "Default")
      (node (ref "U1") (pin "93") (pinfunction "PF4_(ADC4/TCK)_93") (pintype "bidirectional"))
    )
    (net (code "90") (name "unconnected-(U1-PF5_(ADC5{slash}TMS)-Pad92)") (class "Default")
      (node (ref "U1") (pin "92") (pinfunction "PF5_(ADC5/TMS)_92") (pintype "bidirectional"))
    )
    (net (code "91") (name "unconnected-(U1-PF6_(ADC6{slash}TDO)-Pad91)") (class "Default")
      (node (ref "U1") (pin "91") (pinfunction "PF6_(ADC6/TDO)_91") (pintype "bidirectional"))
    )
    (net (code "92") (name "unconnected-(U1-PF7_(ADC7{slash}TDI)-Pad90)") (class "Default")
      (node (ref "U1") (pin "90") (pinfunction "PF7_(ADC7/TDI)_90") (pintype "bidirectional"))
    )
    (net (code "93") (name "unconnected-(U1-PG0_(~{WR})-Pad51)") (class "Default")
      (node (ref "U1") (pin "51") (pinfunction "PG0_(~{WR})_51") (pintype "bidirectional"))
    )
    (net (code "94") (name "unconnected-(U1-PG1_(~{RD})-Pad52)") (class "Default")
      (node (ref "U1") (pin "52") (pinfunction "PG1_(~{RD})_52") (pintype "bidirectional"))
    )
    (net (code "95") (name "unconnected-(U1-PG2_(ALE)-Pad70)") (class "Default")
      (node (ref "U1") (pin "70") (pinfunction "PG2_(ALE)_70") (pintype "bidirectional"))
    )
    (net (code "96") (name "unconnected-(U1-PJ2_(XCK3{slash}PCINT11)-Pad65)") (class "Default")
      (node (ref "U1") (pin "65") (pinfunction "PJ2_(XCK3/PCINT11)_65") (pintype "bidirectional"))
    )
    (net (code "97") (name "unconnected-(U1-PJ3_(PCINT12)-Pad66)") (class "Default")
      (node (ref "U1") (pin "66") (pinfunction "PJ3_(PCINT12)_66") (pintype "bidirectional"))
    )
    (net (code "98") (name "unconnected-(U1-PJ4_(PCINT13)-Pad67)") (class "Default")
      (node (ref "U1") (pin "67") (pinfunction "PJ4_(PCINT13)_67") (pintype "bidirectional"))
    )
    (net (code "99") (name "unconnected-(U1-PJ5_(PCINT14)-Pad68)") (class "Default")
      (node (ref "U1") (pin "68") (pinfunction "PJ5_(PCINT14)_68") (pintype "bidirectional"))
    )
    (net (code "100") (name "unconnected-(U1-PJ6_(PCINT15)-Pad69)") (class "Default")
      (node (ref "U1") (pin "69") (pinfunction "PJ6_(PCINT15)_69") (pintype "bidirectional"))
    )
    (net (code "101") (name "unconnected-(U1-PJ7-Pad79)") (class "Default")
      (node (ref "U1") (pin "79") (pinfunction "PJ7_79") (pintype "bidirectional"))
    )
    (net (code "102") (name "unconnected-(U1-PK3_(ADC11{slash}PCINT19)-Pad86)") (class "Default")
      (node (ref "U1") (pin "86") (pinfunction "PK3_(ADC11/PCINT19)_86") (pintype "bidirectional"))
    )
    (net (code "103") (name "unconnected-(U1-PK4_(ADC12{slash}PCINT20)-Pad85)") (class "Default")
      (node (ref "U1") (pin "85") (pinfunction "PK4_(ADC12/PCINT20)_85") (pintype "bidirectional"))
    )
    (net (code "104") (name "unconnected-(U1-PK5_(ADC13{slash}PCINT21)-Pad84)") (class "Default")
      (node (ref "U1") (pin "84") (pinfunction "PK5_(ADC13/PCINT21)_84") (pintype "bidirectional"))
    )
    (net (code "105") (name "unconnected-(U1-PK6_(ADC14{slash}PCINT22)-Pad83)") (class "Default")
      (node (ref "U1") (pin "83") (pinfunction "PK6_(ADC14/PCINT22)_83") (pintype "bidirectional"))
    )
    (net (code "106") (name "unconnected-(U1-PK7_(ADC15{slash}PCINT23)-Pad82)") (class "Default")
      (node (ref "U1") (pin "82") (pinfunction "PK7_(ADC15/PCINT23)_82") (pintype "bidirectional"))
    )
    (net (code "107") (name "unconnected-(U1-PL6-Pad41)") (class "Default")
      (node (ref "U1") (pin "41") (pinfunction "PL6_41") (pintype "bidirectional"))
    )
    (net (code "108") (name "unconnected-(U1-PL7-Pad42)") (class "Default")
      (node (ref "U1") (pin "42") (pinfunction "PL7_42") (pintype "bidirectional"))
    )
    (net (code "109") (name "unconnected-(U3-VREF-Pad5)") (class "Default")
      (node (ref "U3") (pin "5") (pinfunction "VREF_5") (pintype "passive"))
    )
    (net (code "110") (name "unconnected-(U4-Pad4)") (class "Default")
      (node (ref "U4") (pin "4") (pinfunction "4_4") (pintype "passive"))
    )
    (net (code "111") (name "~{RESET}") (class "Default")
      (node (ref "J2") (pin "5") (pinfunction "5_5") (pintype "passive"))
      (node (ref "R2") (pin "1") (pinfunction "1_1") (pintype "passive"))
      (node (ref "S1") (pin "2.1") (pinfunction "2_2.1") (pintype "passive"))
      (node (ref "S1") (pin "2.2") (pinfunction "2_2.2") (pintype "passive"))
      (node (ref "U1") (pin "30") (pinfunction "~{RESET}_30") (pintype "input"))
    )
  )
)
